# RelayDelayAtmel.net
KiCad netlist of a schematic drawn in EAGLE
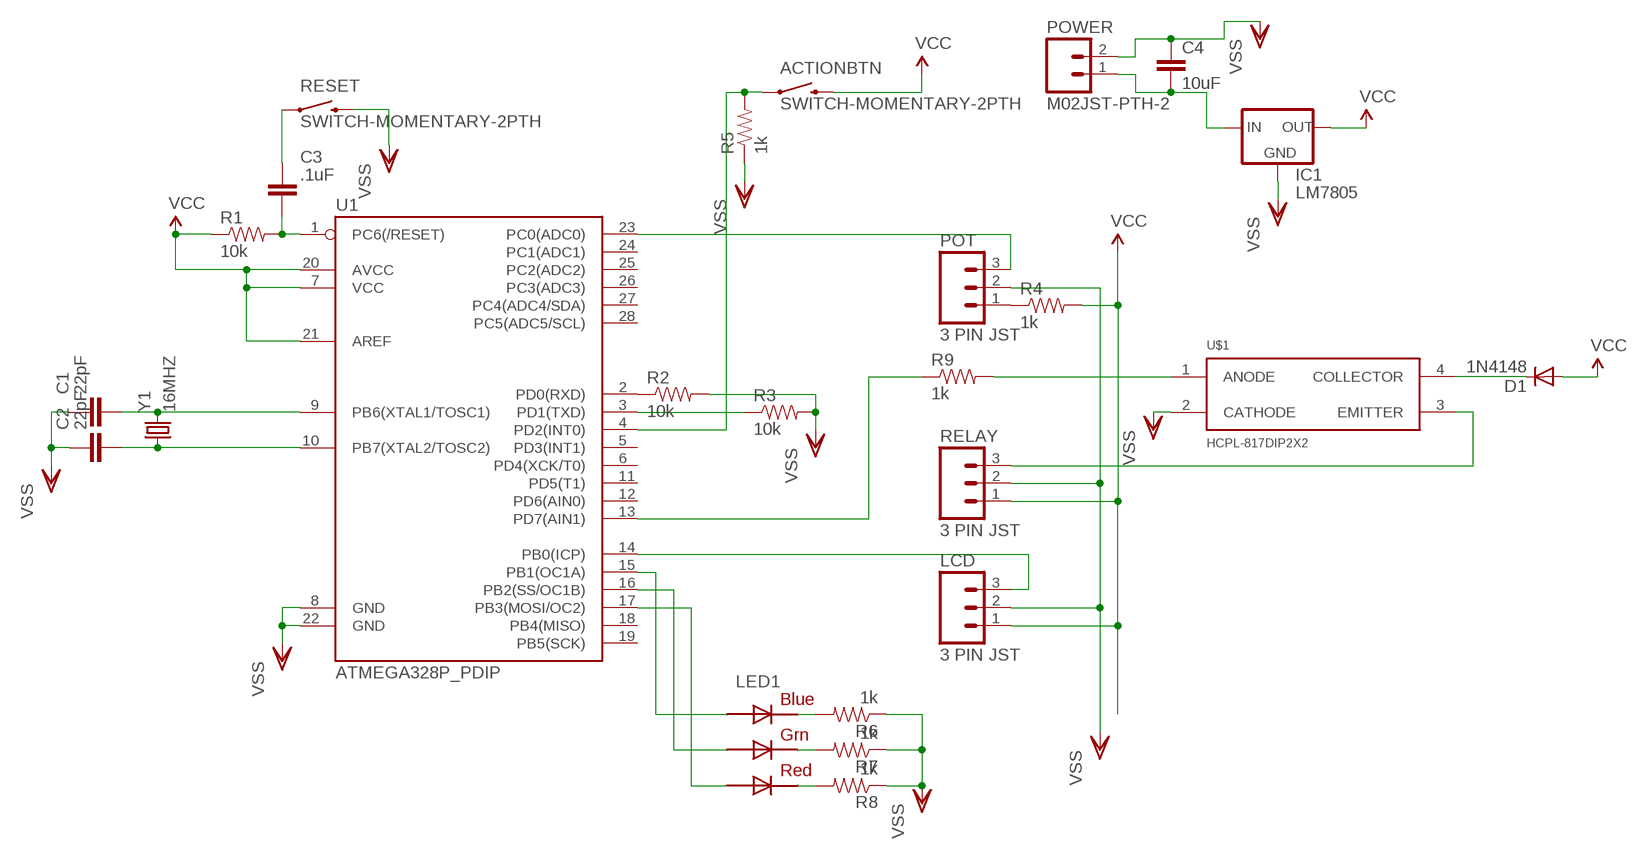
[diagram p0: schematic, sheet 1]

(export (version "E")
  (design (tool "Eeschema 10.0.6"))
  (components
    (comp (ref "ACTIONBTN")
      (value "SWITCH-MOMENTARY-2PTH")
      (footprint "eagle-import:TACTILE-PTH")
      (libsource (lib "eagle-import") (part "SWITCH-MOMENTARY-2PTH"))
    )
    (comp (ref "C1")
      (value "22pF")
      (footprint "eagle-import:C0.1PTH")
      (libsource (lib "eagle-import") (part "CAPACITOR_NPOL-PTH_0.1{dblquote}"))
    )
    (comp (ref "C2")
      (value "22pF")
      (footprint "eagle-import:C0.1PTH")
      (libsource (lib "eagle-import") (part "CAPACITOR_NPOL-PTH_0.1{dblquote}"))
    )
    (comp (ref "C3")
      (value ".1uF")
      (footprint "eagle-import:C0.1PTH")
      (libsource (lib "eagle-import") (part "CAPACITOR_NPOL-PTH_0.1{dblquote}"))
    )
    (comp (ref "C4")
      (value "10uF")
      (footprint "eagle-import:CAP-PTH-SMALLEZ")
      (libsource (lib "eagle-import") (part "CAPEZ"))
    )
    (comp (ref "D1")
      (value "1N4148")
      (footprint "eagle-import:DIODE-1N4001-KIT")
      (libsource (lib "eagle-import") (part "DIODE"))
    )
    (comp (ref "IC1")
      (value "LM7805")
      (footprint "eagle-import:TO-220-ALT")
      (libsource (lib "eagle-import") (part "V_REG_78XX-TO-220"))
    )
    (comp (ref "LCD")
      (value "3 PIN JST")
      (footprint "eagle-import:JST-3-PTH")
      (libsource (lib "eagle-import") (part "M03JST-PTH"))
    )
    (comp (ref "LED1")
      (value "RGBLED5050")
      (footprint "eagle-import:RGBLED5050")
      (libsource (lib "eagle-import") (part "RGBLED5050"))
    )
    (comp (ref "POT")
      (value "3 PIN JST")
      (footprint "eagle-import:JST-3-PTH")
      (libsource (lib "eagle-import") (part "M03JST-PTH"))
    )
    (comp (ref "POWER")
      (value "M02JST-PTH-2")
      (footprint "eagle-import:JST-2-PTH")
      (libsource (lib "eagle-import") (part "M02JST-PTH-2"))
    )
    (comp (ref "R1")
      (value "10k")
      (footprint "eagle-import:AXIAL-0.3")
      (libsource (lib "eagle-import") (part "RESISTORAXIAL-0.3"))
    )
    (comp (ref "R2")
      (value "10k")
      (footprint "eagle-import:AXIAL-0.3")
      (libsource (lib "eagle-import") (part "RESISTORAXIAL-0.3"))
    )
    (comp (ref "R3")
      (value "10k")
      (footprint "eagle-import:AXIAL-0.3")
      (libsource (lib "eagle-import") (part "RESISTORAXIAL-0.3"))
    )
    (comp (ref "R4")
      (value "1k")
      (footprint "eagle-import:AXIAL-0.3")
      (libsource (lib "eagle-import") (part "RESISTORAXIAL-0.3"))
    )
    (comp (ref "R5")
      (value "1k")
      (footprint "eagle-import:AXIAL-0.3")
      (libsource (lib "eagle-import") (part "RESISTORAXIAL-0.3"))
    )
    (comp (ref "R6")
      (value "1k")
      (footprint "eagle-import:AXIAL-0.3")
      (libsource (lib "eagle-import") (part "RESISTORAXIAL-0.3"))
    )
    (comp (ref "R7")
      (value "1k")
      (footprint "eagle-import:AXIAL-0.3")
      (libsource (lib "eagle-import") (part "RESISTORAXIAL-0.3"))
    )
    (comp (ref "R8")
      (value "1k")
      (footprint "eagle-import:AXIAL-0.3")
      (libsource (lib "eagle-import") (part "RESISTORAXIAL-0.3"))
    )
    (comp (ref "R9")
      (value "1k")
      (footprint "eagle-import:AXIAL-0.3")
      (libsource (lib "eagle-import") (part "RESISTORAXIAL-0.3"))
    )
    (comp (ref "RELAY")
      (value "3 PIN JST")
      (footprint "eagle-import:JST-3-PTH")
      (libsource (lib "eagle-import") (part "M03JST-PTH"))
    )
    (comp (ref "RESET")
      (value "SWITCH-MOMENTARY-2PTH")
      (footprint "eagle-import:TACTILE-PTH")
      (libsource (lib "eagle-import") (part "SWITCH-MOMENTARY-2PTH"))
    )
    (comp (ref "U$1")
      (value "HCPL-817DIP2X2")
      (footprint "eagle-import:DIP")
      (libsource (lib "eagle-import") (part "HCPL-817DIP2X2"))
    )
    (comp (ref "U1")
      (value "ATMEGA328P_PDIP")
      (footprint "eagle-import:DIL28-3")
      (libsource (lib "eagle-import") (part "ATMEGA328P_PDIP"))
    )
    (comp (ref "Y1")
      (value "16MHZ")
      (footprint "eagle-import:HC49US")
      (libsource (lib "eagle-import") (part "CRYSTALHC49US"))
    )
  )
  (nets
    (net (code "1") (name "Net-(C3-Pad1)") (class "Default")
      (node (ref "C3") (pin "1") (pinfunction "1_1") (pintype "passive"))
      (node (ref "RESET") (pin "1") (pinfunction "1_1") (pintype "passive"))
    )
    (net (code "2") (name "Net-(C4-Pad2)") (class "Default")
      (node (ref "C4") (pin "2") (pinfunction "2_2") (pintype "passive"))
      (node (ref "IC1") (pin "IN") (pinfunction "IN_IN") (pintype "input"))
      (node (ref "POWER") (pin "1") (pinfunction "1_1") (pintype "passive"))
    )
    (net (code "3") (name "Net-(LED1-BLUE_A)") (class "Default")
      (node (ref "LED1") (pin "3") (pinfunction "BLUE_A_3") (pintype "bidirectional"))
      (node (ref "U1") (pin "15") (pinfunction "PB1(OC1A)_15") (pintype "bidirectional"))
    )
    (net (code "4") (name "Net-(LED1-BLUE_C)") (class "Default")
      (node (ref "LED1") (pin "4") (pinfunction "BLUE_C_4") (pintype "bidirectional"))
      (node (ref "R6") (pin "P$2") (pinfunction "2_P$2") (pintype "passive"))
    )
    (net (code "5") (name "Net-(LED1-GREEN_A)") (class "Default")
      (node (ref "LED1") (pin "1") (pinfunction "GREEN_A_1") (pintype "bidirectional"))
      (node (ref "U1") (pin "16") (pinfunction "PB2(SS/OC1B)_16") (pintype "bidirectional"))
    )
    (net (code "6") (name "Net-(LED1-GREEN_C)") (class "Default")
      (node (ref "LED1") (pin "6") (pinfunction "GREEN_C_6") (pintype "bidirectional"))
      (node (ref "R7") (pin "P$2") (pinfunction "2_P$2") (pintype "passive"))
    )
    (net (code "7") (name "Net-(LED1-RED_A)") (class "Default")
      (node (ref "LED1") (pin "2") (pinfunction "RED_A_2") (pintype "bidirectional"))
      (node (ref "U1") (pin "17") (pinfunction "PB3(MOSI/OC2)_17") (pintype "bidirectional"))
    )
    (net (code "8") (name "Net-(LED1-RED_C)") (class "Default")
      (node (ref "LED1") (pin "5") (pinfunction "RED_C_5") (pintype "bidirectional"))
      (node (ref "R8") (pin "P$2") (pinfunction "2_P$2") (pintype "passive"))
    )
    (net (code "9") (name "Net-(R1-2)") (class "Default")
      (node (ref "C3") (pin "2") (pinfunction "2_2") (pintype "passive"))
      (node (ref "R1") (pin "P$2") (pinfunction "2_P$2") (pintype "passive"))
      (node (ref "U1") (pin "1") (pinfunction "PC6(/RESET)_1") (pintype "bidirectional"))
    )
    (net (code "10") (name "Net-(R2-1)") (class "Default")
      (node (ref "R2") (pin "P$1") (pinfunction "1_P$1") (pintype "passive"))
      (node (ref "U1") (pin "2") (pinfunction "PD0(RXD)_2") (pintype "bidirectional"))
    )
    (net (code "11") (name "Net-(R3-1)") (class "Default")
      (node (ref "R3") (pin "P$1") (pinfunction "1_P$1") (pintype "passive"))
      (node (ref "U1") (pin "3") (pinfunction "PD1(TXD)_3") (pintype "bidirectional"))
    )
    (net (code "12") (name "Net-(R4-1)") (class "Default")
      (node (ref "POT") (pin "1") (pinfunction "1_1") (pintype "passive"))
      (node (ref "R4") (pin "P$1") (pinfunction "1_P$1") (pintype "passive"))
    )
    (net (code "13") (name "Net-(R5-2)") (class "Default")
      (node (ref "ACTIONBTN") (pin "1") (pinfunction "1_1") (pintype "passive"))
      (node (ref "R5") (pin "P$2") (pinfunction "2_P$2") (pintype "passive"))
      (node (ref "U1") (pin "4") (pinfunction "PD2(INT0)_4") (pintype "bidirectional"))
    )
    (net (code "14") (name "Net-(R9-1)") (class "Default")
      (node (ref "R9") (pin "P$1") (pinfunction "1_P$1") (pintype "passive"))
      (node (ref "U1") (pin "13") (pinfunction "PD7(AIN1)_13") (pintype "bidirectional"))
    )
    (net (code "15") (name "Net-(R9-2)") (class "Default")
      (node (ref "R9") (pin "P$2") (pinfunction "2_P$2") (pintype "passive"))
      (node (ref "U$1") (pin "1") (pinfunction "ANODE_1") (pintype "bidirectional"))
    )
    (net (code "16") (name "Net-(U$1-COLLECTOR)") (class "Default")
      (node (ref "D1") (pin "C") (pinfunction "C_C") (pintype "passive"))
      (node (ref "U$1") (pin "4") (pinfunction "COLLECTOR_4") (pintype "bidirectional"))
    )
    (net (code "17") (name "Net-(U$1-EMITTER)") (class "Default")
      (node (ref "RELAY") (pin "3") (pinfunction "3_3") (pintype "passive"))
      (node (ref "U$1") (pin "3") (pinfunction "EMITTER_3") (pintype "bidirectional"))
    )
    (net (code "18") (name "Net-(U1-PB0(ICP))") (class "Default")
      (node (ref "LCD") (pin "3") (pinfunction "3_3") (pintype "passive"))
      (node (ref "U1") (pin "14") (pinfunction "PB0(ICP)_14") (pintype "bidirectional"))
    )
    (net (code "19") (name "Net-(U1-PB6(XTAL1{slash}TOSC1))") (class "Default")
      (node (ref "C1") (pin "2") (pinfunction "2_2") (pintype "passive"))
      (node (ref "U1") (pin "9") (pinfunction "PB6(XTAL1/TOSC1)_9") (pintype "bidirectional"))
      (node (ref "Y1") (pin "2") (pinfunction "2_2") (pintype "passive"))
    )
    (net (code "20") (name "Net-(U1-PB7(XTAL2{slash}TOSC2))") (class "Default")
      (node (ref "C2") (pin "2") (pinfunction "2_2") (pintype "passive"))
      (node (ref "U1") (pin "10") (pinfunction "PB7(XTAL2/TOSC2)_10") (pintype "bidirectional"))
      (node (ref "Y1") (pin "1") (pinfunction "1_1") (pintype "passive"))
    )
    (net (code "21") (name "Net-(U1-PC0(ADC0))") (class "Default")
      (node (ref "POT") (pin "3") (pinfunction "3_3") (pintype "passive"))
      (node (ref "U1") (pin "23") (pinfunction "PC0(ADC0)_23") (pintype "bidirectional"))
    )
    (net (code "22") (name "VCC") (class "Default")
      (node (ref "ACTIONBTN") (pin "3") (pinfunction "2_3") (pintype "passive"))
      (node (ref "D1") (pin "A") (pinfunction "A_A") (pintype "passive"))
      (node (ref "IC1") (pin "OUT") (pinfunction "OUT_OUT") (pintype "output"))
      (node (ref "LCD") (pin "1") (pinfunction "1_1") (pintype "passive"))
      (node (ref "R1") (pin "P$1") (pinfunction "1_P$1") (pintype "passive"))
      (node (ref "R4") (pin "P$2") (pinfunction "2_P$2") (pintype "passive"))
      (node (ref "RELAY") (pin "1") (pinfunction "1_1") (pintype "passive"))
      (node (ref "U1") (pin "20") (pinfunction "AVCC_20") (pintype "bidirectional"))
      (node (ref "U1") (pin "21") (pinfunction "AREF_21") (pintype "bidirectional"))
      (node (ref "U1") (pin "7") (pinfunction "VCC_7") (pintype "bidirectional"))
    )
    (net (code "23") (name "VSS") (class "Default")
      (node (ref "C1") (pin "1") (pinfunction "1_1") (pintype "passive"))
      (node (ref "C2") (pin "1") (pinfunction "1_1") (pintype "passive"))
      (node (ref "C4") (pin "1") (pinfunction "1_1") (pintype "passive"))
      (node (ref "IC1") (pin "GND") (pinfunction "GND_GND") (pintype "input"))
      (node (ref "LCD") (pin "2") (pinfunction "2_2") (pintype "passive"))
      (node (ref "POT") (pin "2") (pinfunction "2_2") (pintype "passive"))
      (node (ref "POWER") (pin "2") (pinfunction "2_2") (pintype "passive"))
      (node (ref "R2") (pin "P$2") (pinfunction "2_P$2") (pintype "passive"))
      (node (ref "R3") (pin "P$2") (pinfunction "2_P$2") (pintype "passive"))
      (node (ref "R5") (pin "P$1") (pinfunction "1_P$1") (pintype "passive"))
      (node (ref "R6") (pin "P$1") (pinfunction "1_P$1") (pintype "passive"))
      (node (ref "R7") (pin "P$1") (pinfunction "1_P$1") (pintype "passive"))
      (node (ref "R8") (pin "P$1") (pinfunction "1_P$1") (pintype "passive"))
      (node (ref "RELAY") (pin "2") (pinfunction "2_2") (pintype "passive"))
      (node (ref "RESET") (pin "3") (pinfunction "2_3") (pintype "passive"))
      (node (ref "U$1") (pin "2") (pinfunction "CATHODE_2") (pintype "bidirectional"))
      (node (ref "U1") (pin "22") (pinfunction "GND_22") (pintype "bidirectional"))
      (node (ref "U1") (pin "8") (pinfunction "GND_8") (pintype "bidirectional"))
    )
    (net (code "24") (name "unconnected-(U1-PB4(MISO)-Pad18)") (class "Default")
      (node (ref "U1") (pin "18") (pinfunction "PB4(MISO)_18") (pintype "bidirectional"))
    )
    (net (code "25") (name "unconnected-(U1-PB5(SCK)-Pad19)") (class "Default")
      (node (ref "U1") (pin "19") (pinfunction "PB5(SCK)_19") (pintype "bidirectional"))
    )
    (net (code "26") (name "unconnected-(U1-PC1(ADC1)-Pad24)") (class "Default")
      (node (ref "U1") (pin "24") (pinfunction "PC1(ADC1)_24") (pintype "bidirectional"))
    )
    (net (code "27") (name "unconnected-(U1-PC2(ADC2)-Pad25)") (class "Default")
      (node (ref "U1") (pin "25") (pinfunction "PC2(ADC2)_25") (pintype "bidirectional"))
    )
    (net (code "28") (name "unconnected-(U1-PC3(ADC3)-Pad26)") (class "Default")
      (node (ref "U1") (pin "26") (pinfunction "PC3(ADC3)_26") (pintype "bidirectional"))
    )
    (net (code "29") (name "unconnected-(U1-PC4(ADC4{slash}SDA)-Pad27)") (class "Default")
      (node (ref "U1") (pin "27") (pinfunction "PC4(ADC4/SDA)_27") (pintype "bidirectional"))
    )
    (net (code "30") (name "unconnected-(U1-PC5(ADC5{slash}SCL)-Pad28)") (class "Default")
      (node (ref "U1") (pin "28") (pinfunction "PC5(ADC5/SCL)_28") (pintype "bidirectional"))
    )
    (net (code "31") (name "unconnected-(U1-PD3(INT1)-Pad5)") (class "Default")
      (node (ref "U1") (pin "5") (pinfunction "PD3(INT1)_5") (pintype "bidirectional"))
    )
    (net (code "32") (name "unconnected-(U1-PD4(XCK{slash}T0)-Pad6)") (class "Default")
      (node (ref "U1") (pin "6") (pinfunction "PD4(XCK/T0)_6") (pintype "bidirectional"))
    )
    (net (code "33") (name "unconnected-(U1-PD5(T1)-Pad11)") (class "Default")
      (node (ref "U1") (pin "11") (pinfunction "PD5(T1)_11") (pintype "bidirectional"))
    )
    (net (code "34") (name "unconnected-(U1-PD6(AIN0)-Pad12)") (class "Default")
      (node (ref "U1") (pin "12") (pinfunction "PD6(AIN0)_12") (pintype "bidirectional"))
    )
  )
)
